# March.net
KiCad netlist of a schematic drawn in EAGLE
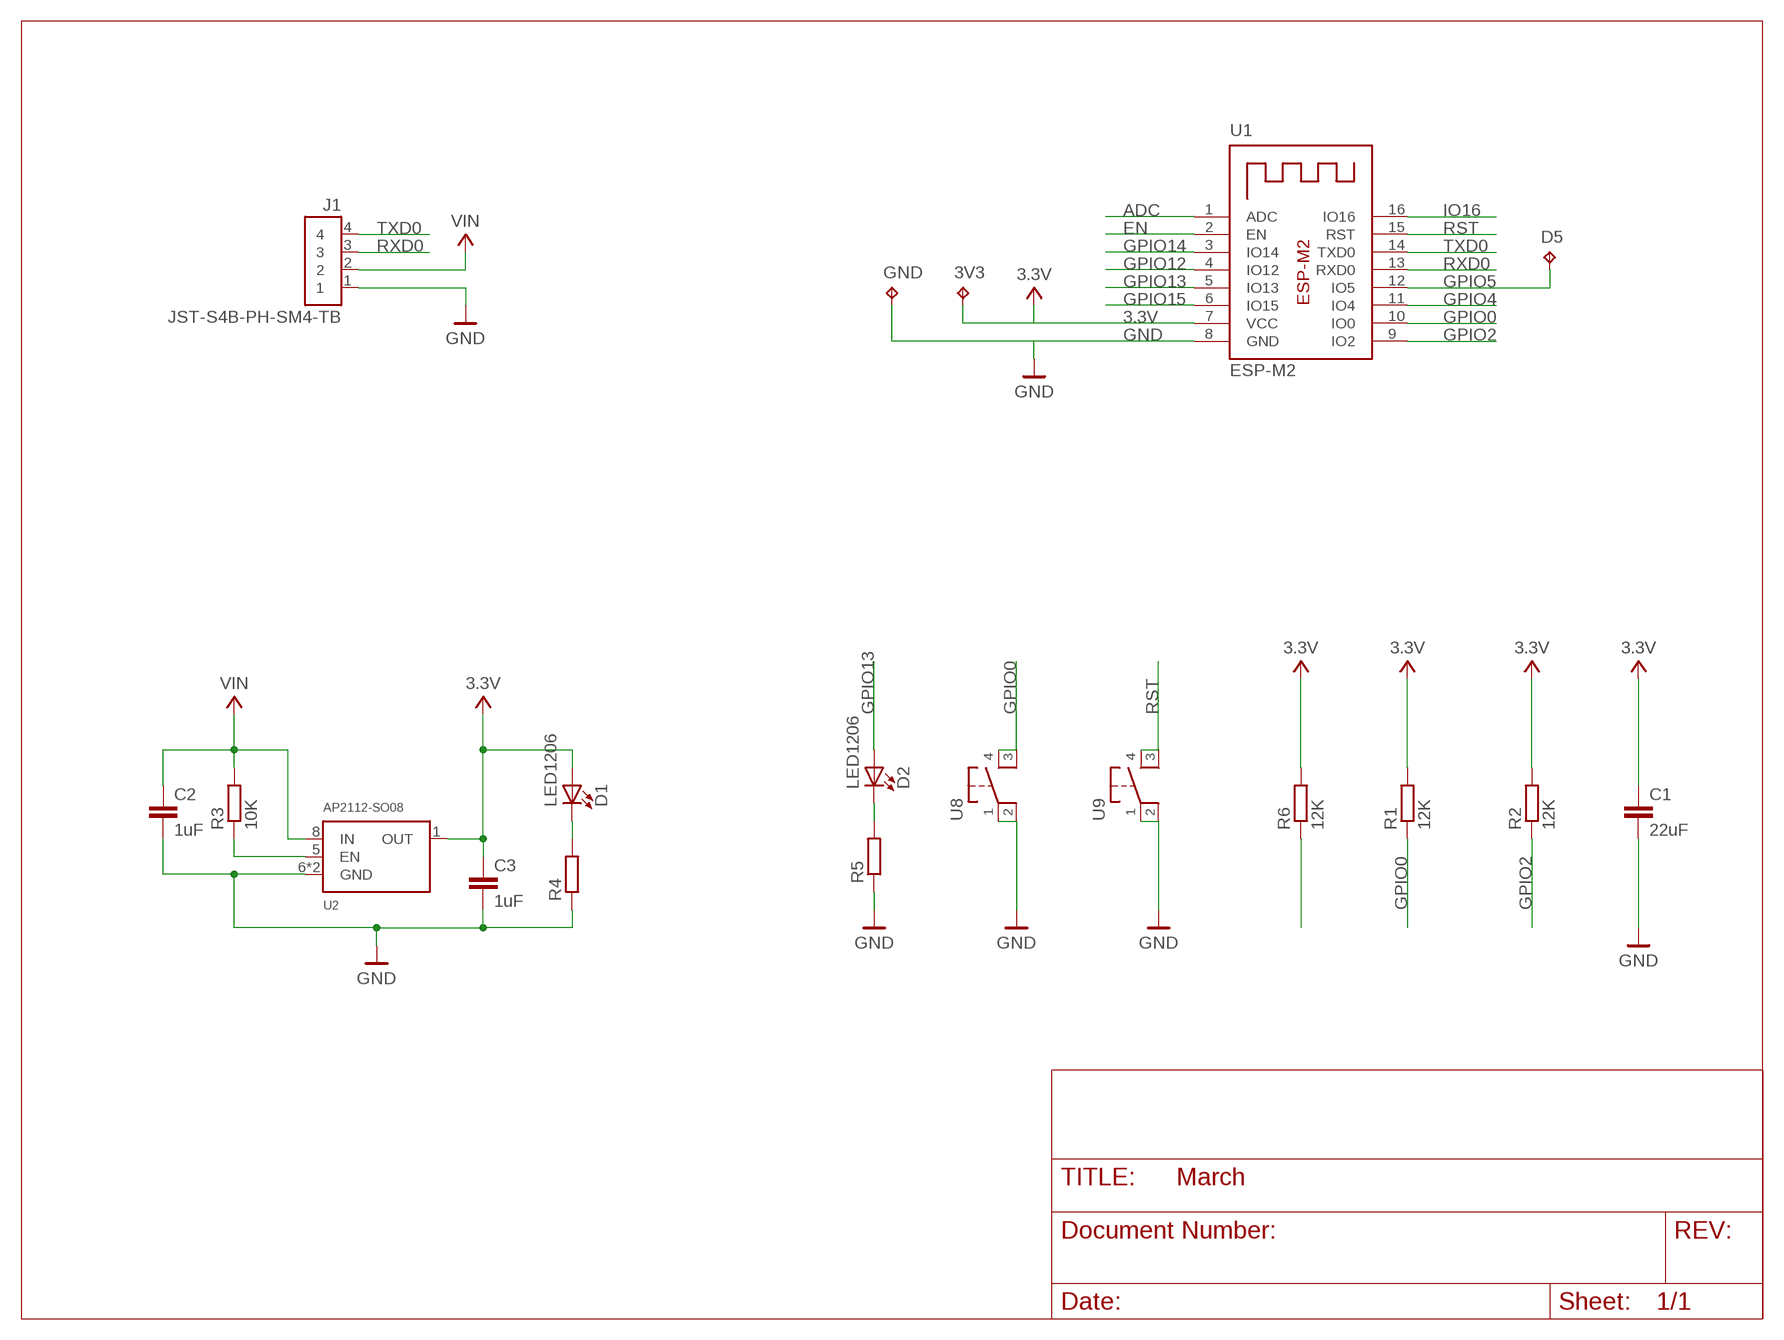
[diagram p0: schematic, sheet 1]

(export (version "E")
  (design (tool "Eeschema 10.0.6"))
  (components
    (comp (ref "3V3")
      (value "TPTP16R")
      (footprint "eagle-import:TP16R")
      (libsource (lib "eagle-import") (part "TPTP16R"))
    )
    (comp (ref "C1")
      (value "22uF")
      (footprint "eagle-import:C1206")
      (libsource (lib "eagle-import") (part "C-EUC1206"))
    )
    (comp (ref "C2")
      (value "1uF")
      (footprint "eagle-import:C1206")
      (libsource (lib "eagle-import") (part "C-EUC1206"))
    )
    (comp (ref "C3")
      (value "1uF")
      (footprint "eagle-import:C1206")
      (libsource (lib "eagle-import") (part "C-EUC1206"))
    )
    (comp (ref "D1")
      (value "LED1206")
      (footprint "eagle-import:LED1206")
      (libsource (lib "eagle-import") (part "LED1206"))
    )
    (comp (ref "D2")
      (value "LED1206")
      (footprint "eagle-import:LED1206")
      (libsource (lib "eagle-import") (part "LED1206"))
    )
    (comp (ref "D5")
      (value "TPTP16R")
      (footprint "eagle-import:TP16R")
      (libsource (lib "eagle-import") (part "TPTP16R"))
    )
    (comp (ref "GND")
      (value "TPTP16R")
      (footprint "eagle-import:TP16R")
      (libsource (lib "eagle-import") (part "TPTP16R"))
    )
    (comp (ref "J1")
      (value "JST-S4B-PH-SM4-TB")
      (footprint "eagle-import:JST-S4B-PH-SM4-TB")
      (libsource (lib "eagle-import") (part "JST-S4B-PH-SM4-TB"))
    )
    (comp (ref "R1")
      (value "12K")
      (footprint "eagle-import:R1206")
      (libsource (lib "eagle-import") (part "R-EU_R1206"))
    )
    (comp (ref "R2")
      (value "12K")
      (footprint "eagle-import:R1206")
      (libsource (lib "eagle-import") (part "R-EU_R1206"))
    )
    (comp (ref "R3")
      (value "10K")
      (footprint "eagle-import:R1206")
      (libsource (lib "eagle-import") (part "R-EU_R1206"))
    )
    (comp (ref "R4")
      (value "R-EU_R1206")
      (footprint "eagle-import:R1206")
      (libsource (lib "eagle-import") (part "resistor_348_R-EU_R1206"))
    )
    (comp (ref "R5")
      (value "R-EU_R1206")
      (footprint "eagle-import:R1206")
      (libsource (lib "eagle-import") (part "resistor_348_R-EU_R1206"))
    )
    (comp (ref "R6")
      (value "12K")
      (footprint "eagle-import:R1206")
      (libsource (lib "eagle-import") (part "R-EU_R1206"))
    )
    (comp (ref "U1")
      (value "ESP-M2")
      (footprint "eagle-import:ESP-M2")
      (libsource (lib "eagle-import") (part "ESP-M2"))
    )
    (comp (ref "U2")
      (value "AP2112-SO08")
      (footprint "eagle-import:SO08")
      (libsource (lib "eagle-import") (part "AP2112-SO08"))
    )
    (comp (ref "U8")
      (value "PTS647")
      (footprint "eagle-import:PTS647")
      (libsource (lib "eagle-import") (part "PTS647"))
    )
    (comp (ref "U9")
      (value "PTS647")
      (footprint "eagle-import:PTS647")
      (libsource (lib "eagle-import") (part "PTS647"))
    )
  )
  (nets
    (net (code "1") (name "/ADC") (class "Default")
      (node (ref "U1") (pin "1") (pinfunction "ADC_1") (pintype "input"))
    )
    (net (code "2") (name "/EN") (class "Default")
      (node (ref "R6") (pin "1") (pinfunction "1_1") (pintype "passive"))
      (node (ref "U1") (pin "2") (pinfunction "EN_2") (pintype "input"))
    )
    (net (code "3") (name "/GPIO0") (class "Default")
      (node (ref "R1") (pin "1") (pinfunction "1_1") (pintype "passive"))
      (node (ref "U1") (pin "10") (pinfunction "IO0_10") (pintype "bidirectional"))
      (node (ref "U8") (pin "3") (pinfunction "3_3") (pintype "bidirectional"))
      (node (ref "U8") (pin "4") (pinfunction "4_4") (pintype "bidirectional"))
    )
    (net (code "4") (name "/GPIO2") (class "Default")
      (node (ref "R2") (pin "1") (pinfunction "1_1") (pintype "passive"))
      (node (ref "U1") (pin "9") (pinfunction "IO2_9") (pintype "bidirectional"))
    )
    (net (code "5") (name "/GPIO4") (class "Default")
      (node (ref "U1") (pin "11") (pinfunction "IO4_11") (pintype "bidirectional"))
    )
    (net (code "6") (name "/GPIO5") (class "Default")
      (node (ref "D5") (pin "TP") (pinfunction "TP_TP") (pintype "input"))
      (node (ref "U1") (pin "12") (pinfunction "IO5_12") (pintype "bidirectional"))
    )
    (net (code "7") (name "/GPIO12") (class "Default")
      (node (ref "U1") (pin "4") (pinfunction "IO12_4") (pintype "bidirectional"))
    )
    (net (code "8") (name "/GPIO13") (class "Default")
      (node (ref "D2") (pin "2") (pinfunction "A_2") (pintype "passive"))
      (node (ref "U1") (pin "5") (pinfunction "IO13_5") (pintype "bidirectional"))
    )
    (net (code "9") (name "/GPIO14") (class "Default")
      (node (ref "U1") (pin "3") (pinfunction "IO14_3") (pintype "bidirectional"))
    )
    (net (code "10") (name "/GPIO15") (class "Default")
      (node (ref "U1") (pin "6") (pinfunction "IO15_6") (pintype "bidirectional"))
    )
    (net (code "11") (name "/IO16") (class "Default")
      (node (ref "U1") (pin "16") (pinfunction "IO16_16") (pintype "bidirectional"))
    )
    (net (code "12") (name "/RST") (class "Default")
      (node (ref "U1") (pin "15") (pinfunction "RST_15") (pintype "input"))
      (node (ref "U9") (pin "3") (pinfunction "3_3") (pintype "bidirectional"))
      (node (ref "U9") (pin "4") (pinfunction "4_4") (pintype "bidirectional"))
    )
    (net (code "13") (name "/RXD0") (class "Default")
      (node (ref "J1") (pin "3") (pinfunction "3_3") (pintype "bidirectional"))
      (node (ref "U1") (pin "13") (pinfunction "RXD0_13") (pintype "input"))
    )
    (net (code "14") (name "/TXD0") (class "Default")
      (node (ref "J1") (pin "4") (pinfunction "4_4") (pintype "bidirectional"))
      (node (ref "U1") (pin "14") (pinfunction "TXD0_14") (pintype "output"))
    )
    (net (code "15") (name "3.3V") (class "Default")
      (node (ref "3V3") (pin "TP") (pinfunction "TP_TP") (pintype "input"))
      (node (ref "C1") (pin "1") (pinfunction "1_1") (pintype "passive"))
      (node (ref "C3") (pin "1") (pinfunction "1_1") (pintype "passive"))
      (node (ref "D1") (pin "2") (pinfunction "A_2") (pintype "passive"))
      (node (ref "R1") (pin "2") (pinfunction "2_2") (pintype "passive"))
      (node (ref "R2") (pin "2") (pinfunction "2_2") (pintype "passive"))
      (node (ref "R6") (pin "2") (pinfunction "2_2") (pintype "passive"))
      (node (ref "U1") (pin "7") (pinfunction "VCC_7") (pintype "power_in"))
      (node (ref "U2") (pin "1") (pinfunction "OUT_1") (pintype "power_in"))
    )
    (net (code "16") (name "GND") (class "Default")
      (node (ref "C1") (pin "2") (pinfunction "2_2") (pintype "passive"))
      (node (ref "C2") (pin "2") (pinfunction "2_2") (pintype "passive"))
      (node (ref "C3") (pin "2") (pinfunction "2_2") (pintype "passive"))
      (node (ref "GND") (pin "TP") (pinfunction "TP_TP") (pintype "input"))
      (node (ref "J1") (pin "1") (pinfunction "1_1") (pintype "bidirectional"))
      (node (ref "R4") (pin "1") (pinfunction "1_1") (pintype "passive"))
      (node (ref "R5") (pin "1") (pinfunction "1_1") (pintype "passive"))
      (node (ref "U1") (pin "8") (pinfunction "GND_8") (pintype "power_in"))
      (node (ref "U2") (pin "6") (pinfunction "GND_6") (pintype "power_in"))
      (node (ref "U2") (pin "7") (pinfunction "GND_7") (pintype "power_in"))
      (node (ref "U8") (pin "1") (pinfunction "1_1") (pintype "bidirectional"))
      (node (ref "U8") (pin "2") (pinfunction "2_2") (pintype "bidirectional"))
      (node (ref "U9") (pin "1") (pinfunction "1_1") (pintype "bidirectional"))
      (node (ref "U9") (pin "2") (pinfunction "2_2") (pintype "bidirectional"))
    )
    (net (code "17") (name "Net-(D1-C)") (class "Default")
      (node (ref "D1") (pin "1") (pinfunction "C_1") (pintype "passive"))
      (node (ref "R4") (pin "2") (pinfunction "2_2") (pintype "passive"))
    )
    (net (code "18") (name "Net-(D2-C)") (class "Default")
      (node (ref "D2") (pin "1") (pinfunction "C_1") (pintype "passive"))
      (node (ref "R5") (pin "2") (pinfunction "2_2") (pintype "passive"))
    )
    (net (code "19") (name "Net-(U2-EN)") (class "Default")
      (node (ref "R3") (pin "1") (pinfunction "1_1") (pintype "passive"))
      (node (ref "U2") (pin "5") (pinfunction "EN_5") (pintype "input"))
    )
    (net (code "20") (name "VIN") (class "Default")
      (node (ref "C2") (pin "1") (pinfunction "1_1") (pintype "passive"))
      (node (ref "J1") (pin "2") (pinfunction "2_2") (pintype "bidirectional"))
      (node (ref "R3") (pin "2") (pinfunction "2_2") (pintype "passive"))
      (node (ref "U2") (pin "8") (pinfunction "IN_8") (pintype "power_in"))
    )
  )
)
